# F407.net
KiCad netlist of a schematic drawn in EasyEDA Pro
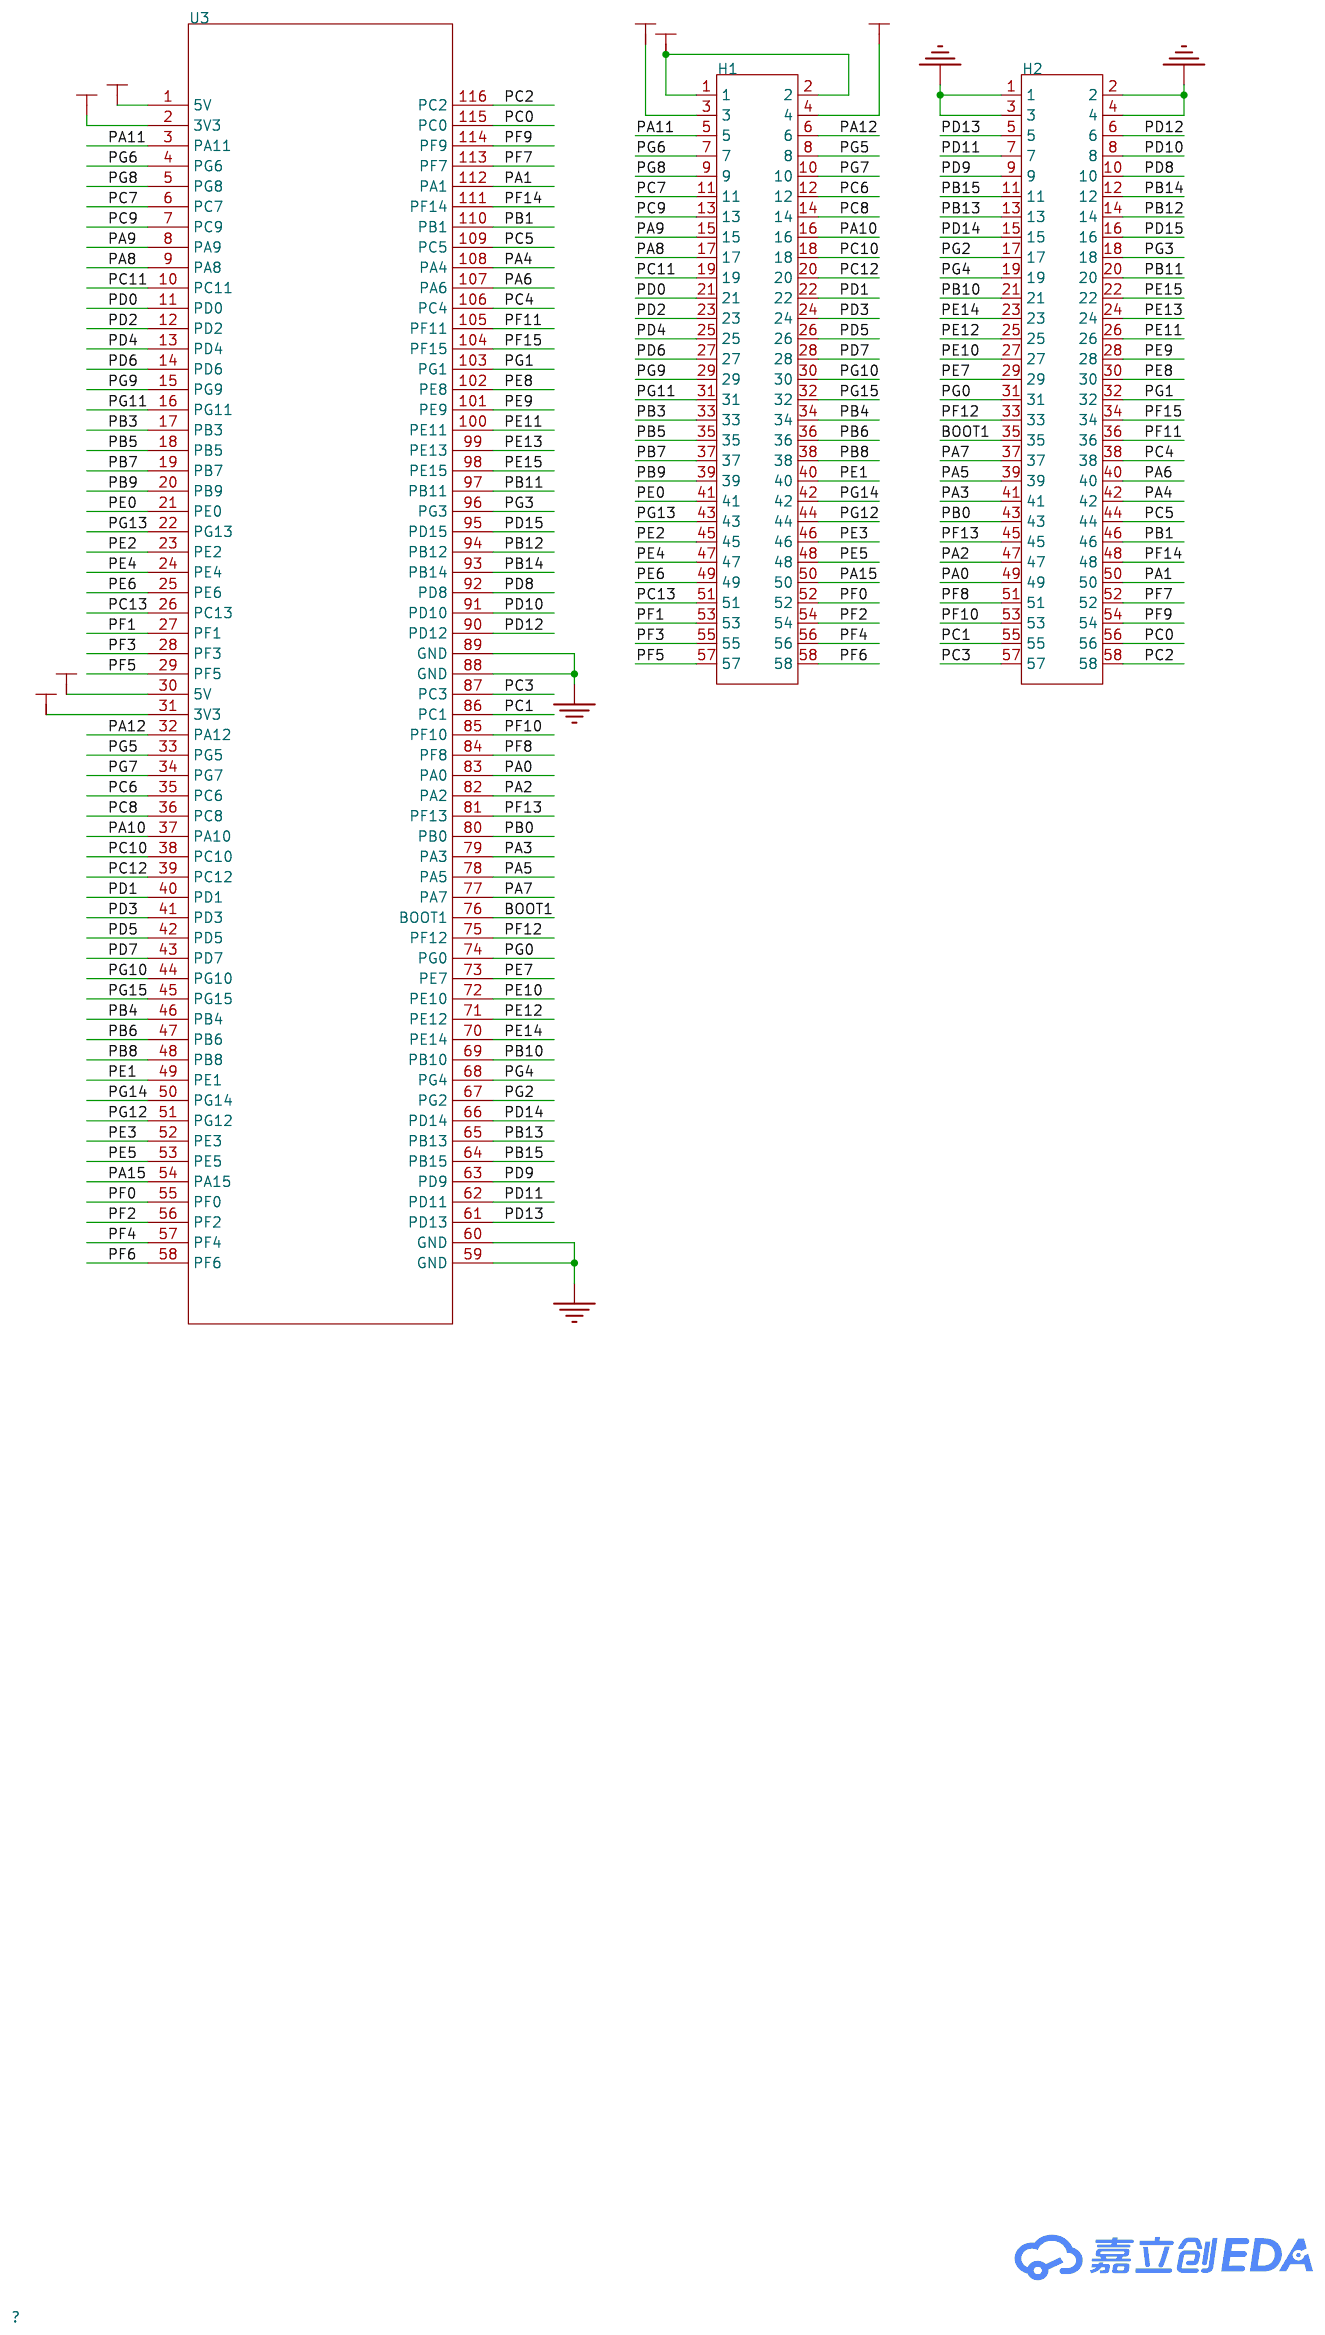
[diagram p0: schematic sheet]

(export (version "E")
  (design (tool "Eeschema 10.0.6"))
  (components
    (comp (ref "H1")
      (value "X6521WV-2x29H-C60D30")
      (footprint "easyedapro:HDR-TH_58P-P2.54-V-M-R2-C29-S2.54")
      (fields (field (name "Manufacturer") "XKB Connection(中国星坤)"))
      (libsource (lib "easyedapro") (part "X6521WV-2×29H-C30D60"))
    )
    (comp (ref "H2")
      (value "X6521WV-2x29H-C60D30")
      (footprint "easyedapro:HDR-TH_58P-P2.54-V-M-R2-C29-S2.54")
      (fields (field (name "Manufacturer") "XKB Connection(中国星坤)"))
      (libsource (lib "easyedapro") (part "X6521WV-2×29H-C30D60"))
    )
    (comp (ref "U3")
      (value "~")
      (footprint "easyedapro:F407ZGT6")
      (libsource (lib "easyedapro") (part "F407ZGT6"))
    )
  )
  (nets
    (net (code "1") (name "/BOOT1") (class "Default")
      (node (ref "H2") (pin "35") (pinfunction "35_35") (pintype "unspecified"))
      (node (ref "U3") (pin "76") (pinfunction "BOOT1_76") (pintype "input"))
    )
    (net (code "2") (name "/PA0") (class "Default")
      (node (ref "H2") (pin "49") (pinfunction "49_49") (pintype "unspecified"))
      (node (ref "U3") (pin "83") (pinfunction "PA0_83") (pintype "input"))
    )
    (net (code "3") (name "/PA1") (class "Default")
      (node (ref "H2") (pin "50") (pinfunction "50_50") (pintype "unspecified"))
      (node (ref "U3") (pin "112") (pinfunction "PA1_112") (pintype "input"))
    )
    (net (code "4") (name "/PA2") (class "Default")
      (node (ref "H2") (pin "47") (pinfunction "47_47") (pintype "unspecified"))
      (node (ref "U3") (pin "82") (pinfunction "PA2_82") (pintype "input"))
    )
    (net (code "5") (name "/PA3") (class "Default")
      (node (ref "H2") (pin "41") (pinfunction "41_41") (pintype "unspecified"))
      (node (ref "U3") (pin "79") (pinfunction "PA3_79") (pintype "input"))
    )
    (net (code "6") (name "/PA4") (class "Default")
      (node (ref "H2") (pin "42") (pinfunction "42_42") (pintype "unspecified"))
      (node (ref "U3") (pin "108") (pinfunction "PA4_108") (pintype "input"))
    )
    (net (code "7") (name "/PA5") (class "Default")
      (node (ref "H2") (pin "39") (pinfunction "39_39") (pintype "unspecified"))
      (node (ref "U3") (pin "78") (pinfunction "PA5_78") (pintype "input"))
    )
    (net (code "8") (name "/PA6") (class "Default")
      (node (ref "H2") (pin "40") (pinfunction "40_40") (pintype "unspecified"))
      (node (ref "U3") (pin "107") (pinfunction "PA6_107") (pintype "input"))
    )
    (net (code "9") (name "/PA7") (class "Default")
      (node (ref "H2") (pin "37") (pinfunction "37_37") (pintype "unspecified"))
      (node (ref "U3") (pin "77") (pinfunction "PA7_77") (pintype "input"))
    )
    (net (code "10") (name "/PA8") (class "Default")
      (node (ref "H1") (pin "17") (pinfunction "17_17") (pintype "unspecified"))
      (node (ref "U3") (pin "9") (pinfunction "PA8_9") (pintype "input"))
    )
    (net (code "11") (name "/PA9") (class "Default")
      (node (ref "H1") (pin "15") (pinfunction "15_15") (pintype "unspecified"))
      (node (ref "U3") (pin "8") (pinfunction "PA9_8") (pintype "input"))
    )
    (net (code "12") (name "/PA10") (class "Default")
      (node (ref "H1") (pin "16") (pinfunction "16_16") (pintype "unspecified"))
      (node (ref "U3") (pin "37") (pinfunction "PA10_37") (pintype "input"))
    )
    (net (code "13") (name "/PA11") (class "Default")
      (node (ref "H1") (pin "5") (pinfunction "5_5") (pintype "unspecified"))
      (node (ref "U3") (pin "3") (pinfunction "PA11_3") (pintype "input"))
    )
    (net (code "14") (name "/PA12") (class "Default")
      (node (ref "H1") (pin "6") (pinfunction "6_6") (pintype "unspecified"))
      (node (ref "U3") (pin "32") (pinfunction "PA12_32") (pintype "input"))
    )
    (net (code "15") (name "/PA15") (class "Default")
      (node (ref "H1") (pin "50") (pinfunction "50_50") (pintype "unspecified"))
      (node (ref "U3") (pin "54") (pinfunction "PA15_54") (pintype "input"))
    )
    (net (code "16") (name "/PB0") (class "Default")
      (node (ref "H2") (pin "43") (pinfunction "43_43") (pintype "unspecified"))
      (node (ref "U3") (pin "80") (pinfunction "PB0_80") (pintype "input"))
    )
    (net (code "17") (name "/PB1") (class "Default")
      (node (ref "H2") (pin "46") (pinfunction "46_46") (pintype "unspecified"))
      (node (ref "U3") (pin "110") (pinfunction "PB1_110") (pintype "input"))
    )
    (net (code "18") (name "/PB3") (class "Default")
      (node (ref "H1") (pin "33") (pinfunction "33_33") (pintype "unspecified"))
      (node (ref "U3") (pin "17") (pinfunction "PB3_17") (pintype "input"))
    )
    (net (code "19") (name "/PB4") (class "Default")
      (node (ref "H1") (pin "34") (pinfunction "34_34") (pintype "unspecified"))
      (node (ref "U3") (pin "46") (pinfunction "PB4_46") (pintype "input"))
    )
    (net (code "20") (name "/PB5") (class "Default")
      (node (ref "H1") (pin "35") (pinfunction "35_35") (pintype "unspecified"))
      (node (ref "U3") (pin "18") (pinfunction "PB5_18") (pintype "input"))
    )
    (net (code "21") (name "/PB6") (class "Default")
      (node (ref "H1") (pin "36") (pinfunction "36_36") (pintype "unspecified"))
      (node (ref "U3") (pin "47") (pinfunction "PB6_47") (pintype "input"))
    )
    (net (code "22") (name "/PB7") (class "Default")
      (node (ref "H1") (pin "37") (pinfunction "37_37") (pintype "unspecified"))
      (node (ref "U3") (pin "19") (pinfunction "PB7_19") (pintype "input"))
    )
    (net (code "23") (name "/PB8") (class "Default")
      (node (ref "H1") (pin "38") (pinfunction "38_38") (pintype "unspecified"))
      (node (ref "U3") (pin "48") (pinfunction "PB8_48") (pintype "input"))
    )
    (net (code "24") (name "/PB9") (class "Default")
      (node (ref "H1") (pin "39") (pinfunction "39_39") (pintype "unspecified"))
      (node (ref "U3") (pin "20") (pinfunction "PB9_20") (pintype "input"))
    )
    (net (code "25") (name "/PB10") (class "Default")
      (node (ref "H2") (pin "21") (pinfunction "21_21") (pintype "unspecified"))
      (node (ref "U3") (pin "69") (pinfunction "PB10_69") (pintype "input"))
    )
    (net (code "26") (name "/PB11") (class "Default")
      (node (ref "H2") (pin "20") (pinfunction "20_20") (pintype "unspecified"))
      (node (ref "U3") (pin "97") (pinfunction "PB11_97") (pintype "input"))
    )
    (net (code "27") (name "/PB12") (class "Default")
      (node (ref "H2") (pin "14") (pinfunction "14_14") (pintype "unspecified"))
      (node (ref "U3") (pin "94") (pinfunction "PB12_94") (pintype "input"))
    )
    (net (code "28") (name "/PB13") (class "Default")
      (node (ref "H2") (pin "13") (pinfunction "13_13") (pintype "unspecified"))
      (node (ref "U3") (pin "65") (pinfunction "PB13_65") (pintype "input"))
    )
    (net (code "29") (name "/PB14") (class "Default")
      (node (ref "H2") (pin "12") (pinfunction "12_12") (pintype "unspecified"))
      (node (ref "U3") (pin "93") (pinfunction "PB14_93") (pintype "input"))
    )
    (net (code "30") (name "/PB15") (class "Default")
      (node (ref "H2") (pin "11") (pinfunction "11_11") (pintype "unspecified"))
      (node (ref "U3") (pin "64") (pinfunction "PB15_64") (pintype "input"))
    )
    (net (code "31") (name "/PC0") (class "Default")
      (node (ref "H2") (pin "56") (pinfunction "56_56") (pintype "unspecified"))
      (node (ref "U3") (pin "115") (pinfunction "PC0_115") (pintype "input"))
    )
    (net (code "32") (name "/PC1") (class "Default")
      (node (ref "H2") (pin "55") (pinfunction "55_55") (pintype "unspecified"))
      (node (ref "U3") (pin "86") (pinfunction "PC1_86") (pintype "input"))
    )
    (net (code "33") (name "/PC2") (class "Default")
      (node (ref "H2") (pin "58") (pinfunction "58_58") (pintype "unspecified"))
      (node (ref "U3") (pin "116") (pinfunction "PC2_116") (pintype "input"))
    )
    (net (code "34") (name "/PC3") (class "Default")
      (node (ref "H2") (pin "57") (pinfunction "57_57") (pintype "unspecified"))
      (node (ref "U3") (pin "87") (pinfunction "PC3_87") (pintype "input"))
    )
    (net (code "35") (name "/PC4") (class "Default")
      (node (ref "H2") (pin "38") (pinfunction "38_38") (pintype "unspecified"))
      (node (ref "U3") (pin "106") (pinfunction "PC4_106") (pintype "input"))
    )
    (net (code "36") (name "/PC5") (class "Default")
      (node (ref "H2") (pin "44") (pinfunction "44_44") (pintype "unspecified"))
      (node (ref "U3") (pin "109") (pinfunction "PC5_109") (pintype "input"))
    )
    (net (code "37") (name "/PC6") (class "Default")
      (node (ref "H1") (pin "12") (pinfunction "12_12") (pintype "unspecified"))
      (node (ref "U3") (pin "35") (pinfunction "PC6_35") (pintype "input"))
    )
    (net (code "38") (name "/PC7") (class "Default")
      (node (ref "H1") (pin "11") (pinfunction "11_11") (pintype "unspecified"))
      (node (ref "U3") (pin "6") (pinfunction "PC7_6") (pintype "input"))
    )
    (net (code "39") (name "/PC8") (class "Default")
      (node (ref "H1") (pin "14") (pinfunction "14_14") (pintype "unspecified"))
      (node (ref "U3") (pin "36") (pinfunction "PC8_36") (pintype "input"))
    )
    (net (code "40") (name "/PC9") (class "Default")
      (node (ref "H1") (pin "13") (pinfunction "13_13") (pintype "unspecified"))
      (node (ref "U3") (pin "7") (pinfunction "PC9_7") (pintype "input"))
    )
    (net (code "41") (name "/PC10") (class "Default")
      (node (ref "H1") (pin "18") (pinfunction "18_18") (pintype "unspecified"))
      (node (ref "U3") (pin "38") (pinfunction "PC10_38") (pintype "input"))
    )
    (net (code "42") (name "/PC11") (class "Default")
      (node (ref "H1") (pin "19") (pinfunction "19_19") (pintype "unspecified"))
      (node (ref "U3") (pin "10") (pinfunction "PC11_10") (pintype "input"))
    )
    (net (code "43") (name "/PC12") (class "Default")
      (node (ref "H1") (pin "20") (pinfunction "20_20") (pintype "unspecified"))
      (node (ref "U3") (pin "39") (pinfunction "PC12_39") (pintype "input"))
    )
    (net (code "44") (name "/PC13") (class "Default")
      (node (ref "H1") (pin "51") (pinfunction "51_51") (pintype "unspecified"))
      (node (ref "U3") (pin "26") (pinfunction "PC13_26") (pintype "input"))
    )
    (net (code "45") (name "/PD0") (class "Default")
      (node (ref "H1") (pin "21") (pinfunction "21_21") (pintype "unspecified"))
      (node (ref "U3") (pin "11") (pinfunction "PD0_11") (pintype "input"))
    )
    (net (code "46") (name "/PD1") (class "Default")
      (node (ref "H1") (pin "22") (pinfunction "22_22") (pintype "unspecified"))
      (node (ref "U3") (pin "40") (pinfunction "PD1_40") (pintype "input"))
    )
    (net (code "47") (name "/PD2") (class "Default")
      (node (ref "H1") (pin "23") (pinfunction "23_23") (pintype "unspecified"))
      (node (ref "U3") (pin "12") (pinfunction "PD2_12") (pintype "input"))
    )
    (net (code "48") (name "/PD3") (class "Default")
      (node (ref "H1") (pin "24") (pinfunction "24_24") (pintype "unspecified"))
      (node (ref "U3") (pin "41") (pinfunction "PD3_41") (pintype "input"))
    )
    (net (code "49") (name "/PD4") (class "Default")
      (node (ref "H1") (pin "25") (pinfunction "25_25") (pintype "unspecified"))
      (node (ref "U3") (pin "13") (pinfunction "PD4_13") (pintype "input"))
    )
    (net (code "50") (name "/PD5") (class "Default")
      (node (ref "H1") (pin "26") (pinfunction "26_26") (pintype "unspecified"))
      (node (ref "U3") (pin "42") (pinfunction "PD5_42") (pintype "input"))
    )
    (net (code "51") (name "/PD6") (class "Default")
      (node (ref "H1") (pin "27") (pinfunction "27_27") (pintype "unspecified"))
      (node (ref "U3") (pin "14") (pinfunction "PD6_14") (pintype "input"))
    )
    (net (code "52") (name "/PD7") (class "Default")
      (node (ref "H1") (pin "28") (pinfunction "28_28") (pintype "unspecified"))
      (node (ref "U3") (pin "43") (pinfunction "PD7_43") (pintype "input"))
    )
    (net (code "53") (name "/PD8") (class "Default")
      (node (ref "H2") (pin "10") (pinfunction "10_10") (pintype "unspecified"))
      (node (ref "U3") (pin "92") (pinfunction "PD8_92") (pintype "input"))
    )
    (net (code "54") (name "/PD9") (class "Default")
      (node (ref "H2") (pin "9") (pinfunction "9_9") (pintype "unspecified"))
      (node (ref "U3") (pin "63") (pinfunction "PD9_63") (pintype "input"))
    )
    (net (code "55") (name "/PD10") (class "Default")
      (node (ref "H2") (pin "8") (pinfunction "8_8") (pintype "unspecified"))
      (node (ref "U3") (pin "91") (pinfunction "PD10_91") (pintype "input"))
    )
    (net (code "56") (name "/PD11") (class "Default")
      (node (ref "H2") (pin "7") (pinfunction "7_7") (pintype "unspecified"))
      (node (ref "U3") (pin "62") (pinfunction "PD11_62") (pintype "input"))
    )
    (net (code "57") (name "/PD12") (class "Default")
      (node (ref "H2") (pin "6") (pinfunction "6_6") (pintype "unspecified"))
      (node (ref "U3") (pin "90") (pinfunction "PD12_90") (pintype "input"))
    )
    (net (code "58") (name "/PD13") (class "Default")
      (node (ref "H2") (pin "5") (pinfunction "5_5") (pintype "unspecified"))
      (node (ref "U3") (pin "61") (pinfunction "PD13_61") (pintype "input"))
    )
    (net (code "59") (name "/PD14") (class "Default")
      (node (ref "H2") (pin "15") (pinfunction "15_15") (pintype "unspecified"))
      (node (ref "U3") (pin "66") (pinfunction "PD14_66") (pintype "input"))
    )
    (net (code "60") (name "/PD15") (class "Default")
      (node (ref "H2") (pin "16") (pinfunction "16_16") (pintype "unspecified"))
      (node (ref "U3") (pin "95") (pinfunction "PD15_95") (pintype "input"))
    )
    (net (code "61") (name "/PE0") (class "Default")
      (node (ref "H1") (pin "41") (pinfunction "41_41") (pintype "unspecified"))
      (node (ref "U3") (pin "21") (pinfunction "PE0_21") (pintype "input"))
    )
    (net (code "62") (name "/PE1") (class "Default")
      (node (ref "H1") (pin "40") (pinfunction "40_40") (pintype "unspecified"))
      (node (ref "U3") (pin "49") (pinfunction "PE1_49") (pintype "input"))
    )
    (net (code "63") (name "/PE2") (class "Default")
      (node (ref "H1") (pin "45") (pinfunction "45_45") (pintype "unspecified"))
      (node (ref "U3") (pin "23") (pinfunction "PE2_23") (pintype "input"))
    )
    (net (code "64") (name "/PE3") (class "Default")
      (node (ref "H1") (pin "46") (pinfunction "46_46") (pintype "unspecified"))
      (node (ref "U3") (pin "52") (pinfunction "PE3_52") (pintype "input"))
    )
    (net (code "65") (name "/PE4") (class "Default")
      (node (ref "H1") (pin "47") (pinfunction "47_47") (pintype "unspecified"))
      (node (ref "U3") (pin "24") (pinfunction "PE4_24") (pintype "input"))
    )
    (net (code "66") (name "/PE5") (class "Default")
      (node (ref "H1") (pin "48") (pinfunction "48_48") (pintype "unspecified"))
      (node (ref "U3") (pin "53") (pinfunction "PE5_53") (pintype "input"))
    )
    (net (code "67") (name "/PE6") (class "Default")
      (node (ref "H1") (pin "49") (pinfunction "49_49") (pintype "unspecified"))
      (node (ref "U3") (pin "25") (pinfunction "PE6_25") (pintype "input"))
    )
    (net (code "68") (name "/PE7") (class "Default")
      (node (ref "H2") (pin "29") (pinfunction "29_29") (pintype "unspecified"))
      (node (ref "U3") (pin "73") (pinfunction "PE7_73") (pintype "input"))
    )
    (net (code "69") (name "/PE8") (class "Default")
      (node (ref "H2") (pin "30") (pinfunction "30_30") (pintype "unspecified"))
      (node (ref "U3") (pin "102") (pinfunction "PE8_102") (pintype "input"))
    )
    (net (code "70") (name "/PE9") (class "Default")
      (node (ref "H2") (pin "28") (pinfunction "28_28") (pintype "unspecified"))
      (node (ref "U3") (pin "101") (pinfunction "PE9_101") (pintype "input"))
    )
    (net (code "71") (name "/PE10") (class "Default")
      (node (ref "H2") (pin "27") (pinfunction "27_27") (pintype "unspecified"))
      (node (ref "U3") (pin "72") (pinfunction "PE10_72") (pintype "input"))
    )
    (net (code "72") (name "/PE11") (class "Default")
      (node (ref "H2") (pin "26") (pinfunction "26_26") (pintype "unspecified"))
      (node (ref "U3") (pin "100") (pinfunction "PE11_100") (pintype "input"))
    )
    (net (code "73") (name "/PE12") (class "Default")
      (node (ref "H2") (pin "25") (pinfunction "25_25") (pintype "unspecified"))
      (node (ref "U3") (pin "71") (pinfunction "PE12_71") (pintype "input"))
    )
    (net (code "74") (name "/PE13") (class "Default")
      (node (ref "H2") (pin "24") (pinfunction "24_24") (pintype "unspecified"))
      (node (ref "U3") (pin "99") (pinfunction "PE13_99") (pintype "input"))
    )
    (net (code "75") (name "/PE14") (class "Default")
      (node (ref "H2") (pin "23") (pinfunction "23_23") (pintype "unspecified"))
      (node (ref "U3") (pin "70") (pinfunction "PE14_70") (pintype "input"))
    )
    (net (code "76") (name "/PE15") (class "Default")
      (node (ref "H2") (pin "22") (pinfunction "22_22") (pintype "unspecified"))
      (node (ref "U3") (pin "98") (pinfunction "PE15_98") (pintype "input"))
    )
    (net (code "77") (name "/PF0") (class "Default")
      (node (ref "H1") (pin "52") (pinfunction "52_52") (pintype "unspecified"))
      (node (ref "U3") (pin "55") (pinfunction "PF0_55") (pintype "input"))
    )
    (net (code "78") (name "/PF1") (class "Default")
      (node (ref "H1") (pin "53") (pinfunction "53_53") (pintype "unspecified"))
      (node (ref "U3") (pin "27") (pinfunction "PF1_27") (pintype "input"))
    )
    (net (code "79") (name "/PF2") (class "Default")
      (node (ref "H1") (pin "54") (pinfunction "54_54") (pintype "unspecified"))
      (node (ref "U3") (pin "56") (pinfunction "PF2_56") (pintype "input"))
    )
    (net (code "80") (name "/PF3") (class "Default")
      (node (ref "H1") (pin "55") (pinfunction "55_55") (pintype "unspecified"))
      (node (ref "U3") (pin "28") (pinfunction "PF3_28") (pintype "input"))
    )
    (net (code "81") (name "/PF4") (class "Default")
      (node (ref "H1") (pin "56") (pinfunction "56_56") (pintype "unspecified"))
      (node (ref "U3") (pin "57") (pinfunction "PF4_57") (pintype "input"))
    )
    (net (code "82") (name "/PF5") (class "Default")
      (node (ref "H1") (pin "57") (pinfunction "57_57") (pintype "unspecified"))
      (node (ref "U3") (pin "29") (pinfunction "PF5_29") (pintype "input"))
    )
    (net (code "83") (name "/PF6") (class "Default")
      (node (ref "H1") (pin "58") (pinfunction "58_58") (pintype "unspecified"))
      (node (ref "U3") (pin "58") (pinfunction "PF6_58") (pintype "input"))
    )
    (net (code "84") (name "/PF7") (class "Default")
      (node (ref "H2") (pin "52") (pinfunction "52_52") (pintype "unspecified"))
      (node (ref "U3") (pin "113") (pinfunction "PF7_113") (pintype "input"))
    )
    (net (code "85") (name "/PF8") (class "Default")
      (node (ref "H2") (pin "51") (pinfunction "51_51") (pintype "unspecified"))
      (node (ref "U3") (pin "84") (pinfunction "PF8_84") (pintype "input"))
    )
    (net (code "86") (name "/PF9") (class "Default")
      (node (ref "H2") (pin "54") (pinfunction "54_54") (pintype "unspecified"))
      (node (ref "U3") (pin "114") (pinfunction "PF9_114") (pintype "input"))
    )
    (net (code "87") (name "/PF10") (class "Default")
      (node (ref "H2") (pin "53") (pinfunction "53_53") (pintype "unspecified"))
      (node (ref "U3") (pin "85") (pinfunction "PF10_85") (pintype "input"))
    )
    (net (code "88") (name "/PF11") (class "Default")
      (node (ref "H2") (pin "36") (pinfunction "36_36") (pintype "unspecified"))
      (node (ref "U3") (pin "105") (pinfunction "PF11_105") (pintype "input"))
    )
    (net (code "89") (name "/PF12") (class "Default")
      (node (ref "H2") (pin "33") (pinfunction "33_33") (pintype "unspecified"))
      (node (ref "U3") (pin "75") (pinfunction "PF12_75") (pintype "input"))
    )
    (net (code "90") (name "/PF13") (class "Default")
      (node (ref "H2") (pin "45") (pinfunction "45_45") (pintype "unspecified"))
      (node (ref "U3") (pin "81") (pinfunction "PF13_81") (pintype "input"))
    )
    (net (code "91") (name "/PF14") (class "Default")
      (node (ref "H2") (pin "48") (pinfunction "48_48") (pintype "unspecified"))
      (node (ref "U3") (pin "111") (pinfunction "PF14_111") (pintype "input"))
    )
    (net (code "92") (name "/PF15") (class "Default")
      (node (ref "H2") (pin "34") (pinfunction "34_34") (pintype "unspecified"))
      (node (ref "U3") (pin "104") (pinfunction "PF15_104") (pintype "input"))
    )
    (net (code "93") (name "/PG0") (class "Default")
      (node (ref "H2") (pin "31") (pinfunction "31_31") (pintype "unspecified"))
      (node (ref "U3") (pin "74") (pinfunction "PG0_74") (pintype "input"))
    )
    (net (code "94") (name "/PG1") (class "Default")
      (node (ref "H2") (pin "32") (pinfunction "32_32") (pintype "unspecified"))
      (node (ref "U3") (pin "103") (pinfunction "PG1_103") (pintype "input"))
    )
    (net (code "95") (name "/PG2") (class "Default")
      (node (ref "H2") (pin "17") (pinfunction "17_17") (pintype "unspecified"))
      (node (ref "U3") (pin "67") (pinfunction "PG2_67") (pintype "input"))
    )
    (net (code "96") (name "/PG3") (class "Default")
      (node (ref "H2") (pin "18") (pinfunction "18_18") (pintype "unspecified"))
      (node (ref "U3") (pin "96") (pinfunction "PG3_96") (pintype "input"))
    )
    (net (code "97") (name "/PG4") (class "Default")
      (node (ref "H2") (pin "19") (pinfunction "19_19") (pintype "unspecified"))
      (node (ref "U3") (pin "68") (pinfunction "PG4_68") (pintype "input"))
    )
    (net (code "98") (name "/PG5") (class "Default")
      (node (ref "H1") (pin "8") (pinfunction "8_8") (pintype "unspecified"))
      (node (ref "U3") (pin "33") (pinfunction "PG5_33") (pintype "input"))
    )
    (net (code "99") (name "/PG6") (class "Default")
      (node (ref "H1") (pin "7") (pinfunction "7_7") (pintype "unspecified"))
      (node (ref "U3") (pin "4") (pinfunction "PG6_4") (pintype "input"))
    )
    (net (code "100") (name "/PG7") (class "Default")
      (node (ref "H1") (pin "10") (pinfunction "10_10") (pintype "unspecified"))
      (node (ref "U3") (pin "34") (pinfunction "PG7_34") (pintype "input"))
    )
    (net (code "101") (name "/PG8") (class "Default")
      (node (ref "H1") (pin "9") (pinfunction "9_9") (pintype "unspecified"))
      (node (ref "U3") (pin "5") (pinfunction "PG8_5") (pintype "input"))
    )
    (net (code "102") (name "/PG9") (class "Default")
      (node (ref "H1") (pin "29") (pinfunction "29_29") (pintype "unspecified"))
      (node (ref "U3") (pin "15") (pinfunction "PG9_15") (pintype "input"))
    )
    (net (code "103") (name "/PG10") (class "Default")
      (node (ref "H1") (pin "30") (pinfunction "30_30") (pintype "unspecified"))
      (node (ref "U3") (pin "44") (pinfunction "PG10_44") (pintype "input"))
    )
    (net (code "104") (name "/PG11") (class "Default")
      (node (ref "H1") (pin "31") (pinfunction "31_31") (pintype "unspecified"))
      (node (ref "U3") (pin "16") (pinfunction "PG11_16") (pintype "input"))
    )
    (net (code "105") (name "/PG12") (class "Default")
      (node (ref "H1") (pin "44") (pinfunction "44_44") (pintype "unspecified"))
      (node (ref "U3") (pin "51") (pinfunction "PG12_51") (pintype "input"))
    )
    (net (code "106") (name "/PG13") (class "Default")
      (node (ref "H1") (pin "43") (pinfunction "43_43") (pintype "unspecified"))
      (node (ref "U3") (pin "22") (pinfunction "PG13_22") (pintype "input"))
    )
    (net (code "107") (name "/PG14") (class "Default")
      (node (ref "H1") (pin "42") (pinfunction "42_42") (pintype "unspecified"))
      (node (ref "U3") (pin "50") (pinfunction "PG14_50") (pintype "input"))
    )
    (net (code "108") (name "/PG15") (class "Default")
      (node (ref "H1") (pin "32") (pinfunction "32_32") (pintype "unspecified"))
      (node (ref "U3") (pin "45") (pinfunction "PG15_45") (pintype "input"))
    )
    (net (code "109") (name "3V3") (class "Default")
      (node (ref "H1") (pin "3") (pinfunction "3_3") (pintype "unspecified"))
      (node (ref "H1") (pin "4") (pinfunction "4_4") (pintype "unspecified"))
      (node (ref "U3") (pin "2") (pinfunction "3V3_2") (pintype "input"))
      (node (ref "U3") (pin "31") (pinfunction "3V3_31") (pintype "input"))
    )
    (net (code "110") (name "5V") (class "Default")
      (node (ref "H1") (pin "1") (pinfunction "1_1") (pintype "unspecified"))
      (node (ref "H1") (pin "2") (pinfunction "2_2") (pintype "unspecified"))
      (node (ref "U3") (pin "1") (pinfunction "5V_1") (pintype "input"))
      (node (ref "U3") (pin "30") (pinfunction "5V_30") (pintype "input"))
    )
    (net (code "111") (name "GND") (class "Default")
      (node (ref "H2") (pin "1") (pinfunction "1_1") (pintype "unspecified"))
      (node (ref "H2") (pin "2") (pinfunction "2_2") (pintype "unspecified"))
      (node (ref "H2") (pin "3") (pinfunction "3_3") (pintype "unspecified"))
      (node (ref "H2") (pin "4") (pinfunction "4_4") (pintype "unspecified"))
      (node (ref "U3") (pin "59") (pinfunction "GND_59") (pintype "input"))
      (node (ref "U3") (pin "60") (pinfunction "GND_60") (pintype "input"))
      (node (ref "U3") (pin "88") (pinfunction "GND_88") (pintype "input"))
      (node (ref "U3") (pin "89") (pinfunction "GND_89") (pintype "input"))
    )
  )
)
